# Board.net
KiCad netlist of a schematic drawn in EAGLE
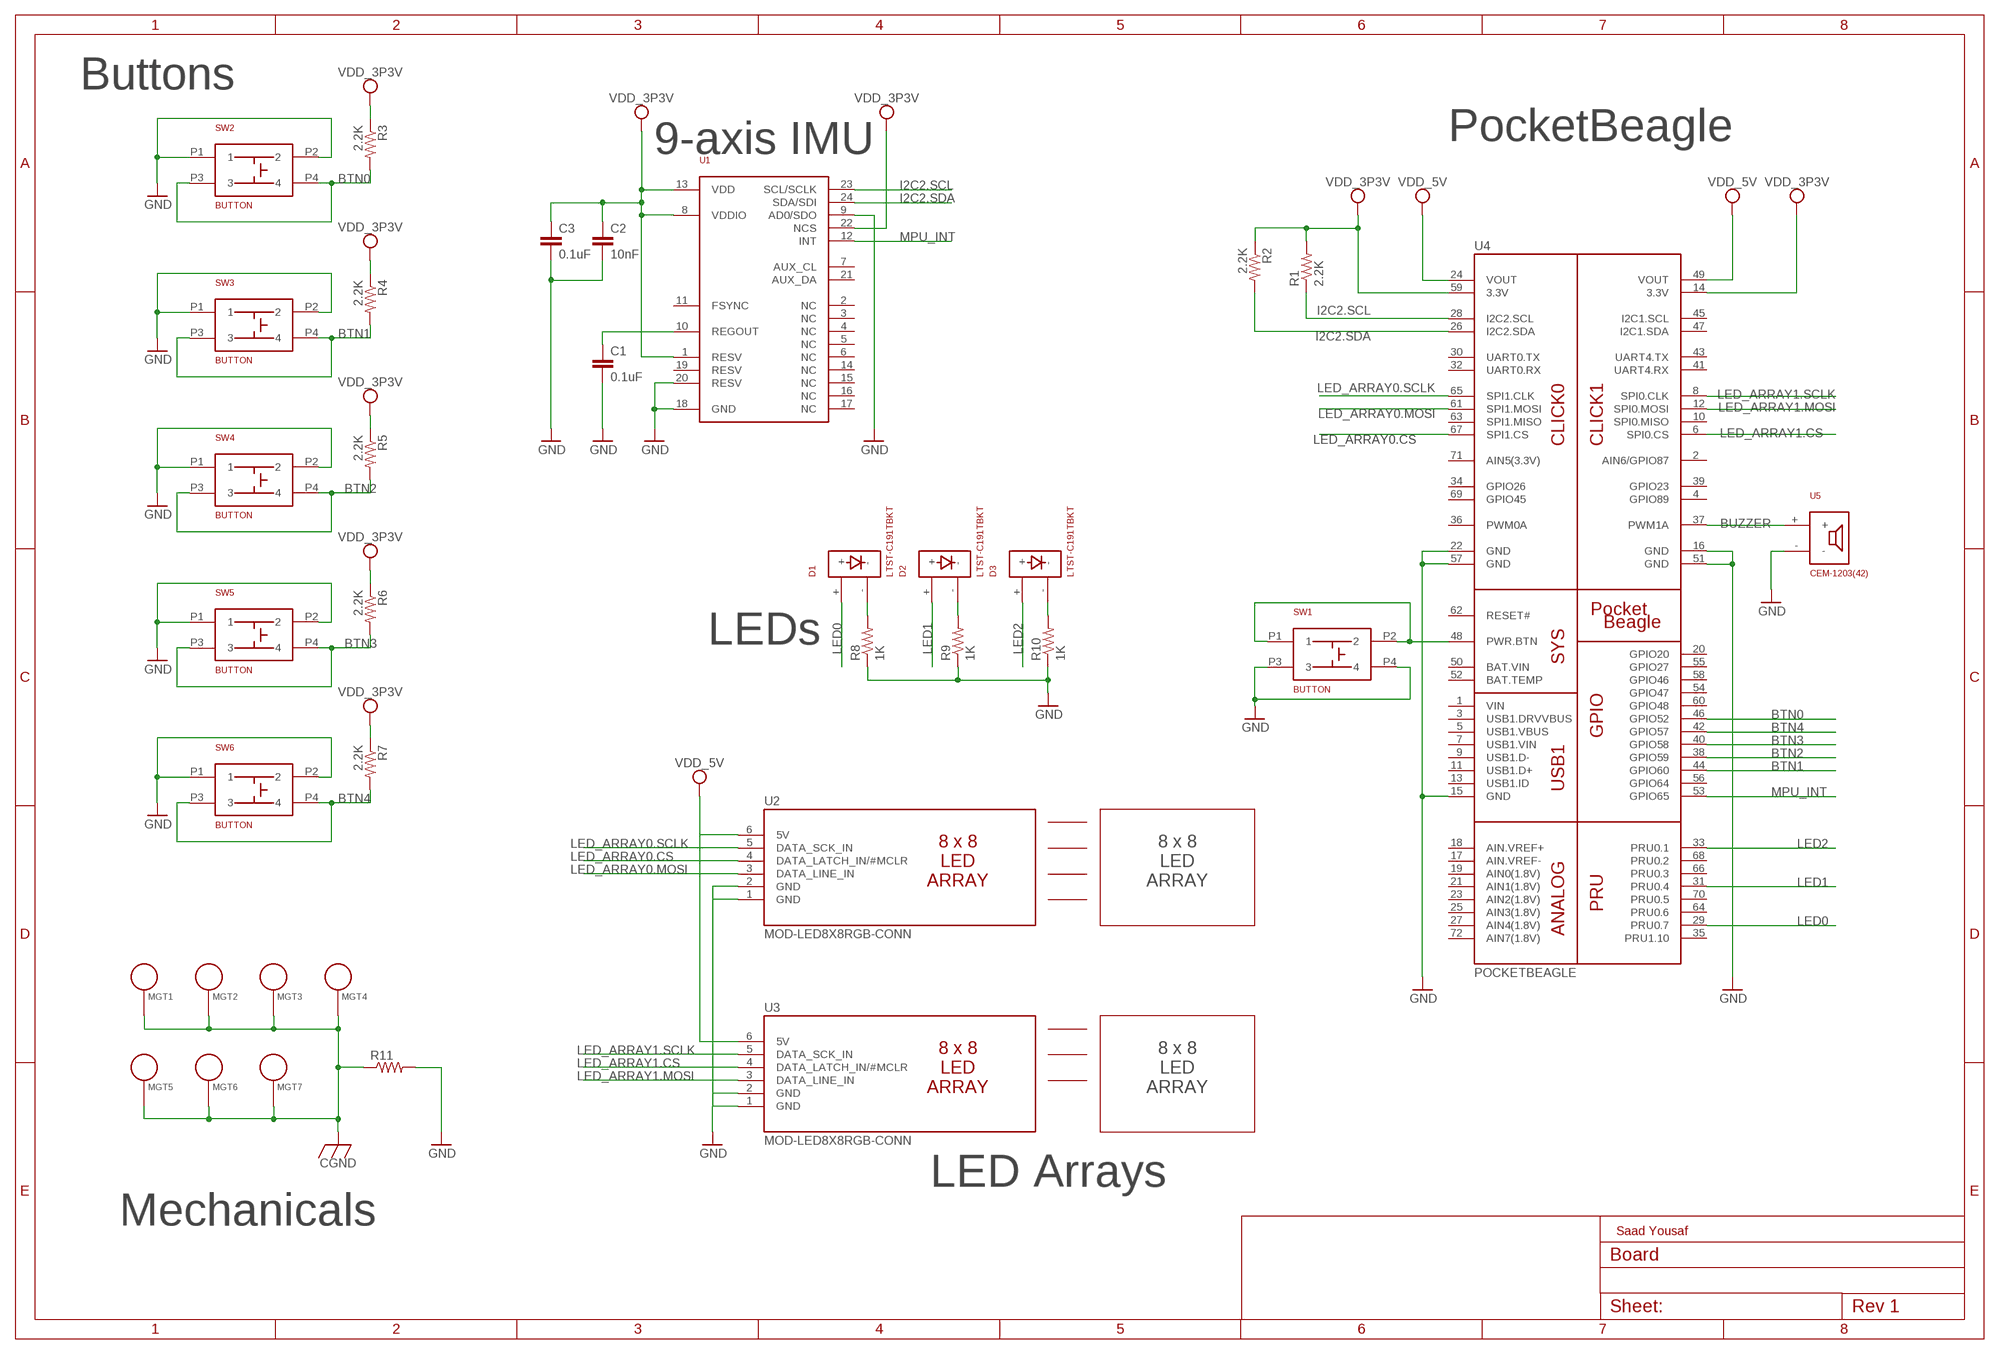
[diagram p0: schematic, sheet 1]

(export (version "E")
  (design (tool "Eeschema 10.0.6"))
  (components
    (comp (ref "C1")
      (value "0.1uF")
      (footprint "eagle-import:C0603")
      (libsource (lib "eagle-import") (part "C_C0603"))
    )
    (comp (ref "C2")
      (value "10nF")
      (footprint "eagle-import:C0603")
      (libsource (lib "eagle-import") (part "C_C0603"))
    )
    (comp (ref "C3")
      (value "0.1uF")
      (footprint "eagle-import:C0603")
      (libsource (lib "eagle-import") (part "C_C0603"))
    )
    (comp (ref "D1")
      (value "LTST-C191TBKT")
      (footprint "eagle-import:SMD-LED")
      (libsource (lib "eagle-import") (part "LTST-C191TBKT"))
    )
    (comp (ref "D2")
      (value "LTST-C191TBKT")
      (footprint "eagle-import:SMD-LED")
      (libsource (lib "eagle-import") (part "LTST-C191TBKT"))
    )
    (comp (ref "D3")
      (value "LTST-C191TBKT")
      (footprint "eagle-import:SMD-LED")
      (libsource (lib "eagle-import") (part "LTST-C191TBKT"))
    )
    (comp (ref "MGT1")
      (value "MOUNTING_HOLE")
      (footprint "eagle-import:MOUNTING_HOLE")
      (libsource (lib "eagle-import") (part "MOUNTING_HOLE"))
    )
    (comp (ref "MGT2")
      (value "MOUNTING_HOLE")
      (footprint "eagle-import:MOUNTING_HOLE")
      (libsource (lib "eagle-import") (part "MOUNTING_HOLE"))
    )
    (comp (ref "MGT3")
      (value "MOUNTING_HOLE")
      (footprint "eagle-import:MOUNTING_HOLE")
      (libsource (lib "eagle-import") (part "MOUNTING_HOLE"))
    )
    (comp (ref "MGT4")
      (value "MOUNTING_HOLE")
      (footprint "eagle-import:MOUNTING_HOLE")
      (libsource (lib "eagle-import") (part "MOUNTING_HOLE"))
    )
    (comp (ref "MGT5")
      (value "MOUNTING_HOLE")
      (footprint "eagle-import:MOUNTING_HOLE")
      (libsource (lib "eagle-import") (part "MOUNTING_HOLE"))
    )
    (comp (ref "MGT6")
      (value "MOUNTING_HOLE")
      (footprint "eagle-import:MOUNTING_HOLE")
      (libsource (lib "eagle-import") (part "MOUNTING_HOLE"))
    )
    (comp (ref "MGT7")
      (value "MOUNTING_HOLE")
      (footprint "eagle-import:MOUNTING_HOLE")
      (libsource (lib "eagle-import") (part "MOUNTING_HOLE"))
    )
    (comp (ref "R1")
      (value "2.2K")
      (footprint "eagle-import:R0603")
      (libsource (lib "eagle-import") (part "R_R0603"))
    )
    (comp (ref "R2")
      (value "2.2K")
      (footprint "eagle-import:R0603")
      (libsource (lib "eagle-import") (part "R_R0603"))
    )
    (comp (ref "R3")
      (value "2.2K")
      (footprint "eagle-import:R0603")
      (libsource (lib "eagle-import") (part "R_R0603"))
    )
    (comp (ref "R4")
      (value "2.2K")
      (footprint "eagle-import:R0603")
      (libsource (lib "eagle-import") (part "R_R0603"))
    )
    (comp (ref "R5")
      (value "2.2K")
      (footprint "eagle-import:R0603")
      (libsource (lib "eagle-import") (part "R_R0603"))
    )
    (comp (ref "R6")
      (value "2.2K")
      (footprint "eagle-import:R0603")
      (libsource (lib "eagle-import") (part "R_R0603"))
    )
    (comp (ref "R7")
      (value "2.2K")
      (footprint "eagle-import:R0603")
      (libsource (lib "eagle-import") (part "R_R0603"))
    )
    (comp (ref "R8")
      (value "1K")
      (footprint "eagle-import:R0603")
      (libsource (lib "eagle-import") (part "R_R0603"))
    )
    (comp (ref "R9")
      (value "1K")
      (footprint "eagle-import:R0603")
      (libsource (lib "eagle-import") (part "R_R0603"))
    )
    (comp (ref "R10")
      (value "1K")
      (footprint "eagle-import:R0603")
      (libsource (lib "eagle-import") (part "R_R0603"))
    )
    (comp (ref "R11")
      (value "R_R0603")
      (footprint "eagle-import:R0603")
      (libsource (lib "eagle-import") (part "R_R0603"))
    )
    (comp (ref "SW1")
      (value "BUTTON")
      (footprint "eagle-import:BTN")
      (libsource (lib "eagle-import") (part "BUTTON"))
    )
    (comp (ref "SW2")
      (value "BUTTON")
      (footprint "eagle-import:BTN")
      (libsource (lib "eagle-import") (part "BUTTON"))
    )
    (comp (ref "SW3")
      (value "BUTTON")
      (footprint "eagle-import:BTN")
      (libsource (lib "eagle-import") (part "BUTTON"))
    )
    (comp (ref "SW4")
      (value "BUTTON")
      (footprint "eagle-import:BTN")
      (libsource (lib "eagle-import") (part "BUTTON"))
    )
    (comp (ref "SW5")
      (value "BUTTON")
      (footprint "eagle-import:BTN")
      (libsource (lib "eagle-import") (part "BUTTON"))
    )
    (comp (ref "SW6")
      (value "BUTTON")
      (footprint "eagle-import:BTN")
      (libsource (lib "eagle-import") (part "BUTTON"))
    )
    (comp (ref "U1")
      (value "MPU-9250")
      (footprint "eagle-import:QFN-3MMX3MM")
      (libsource (lib "eagle-import") (part "MPU-9250"))
    )
    (comp (ref "U2")
      (value "MOD-LED8X8RGB-CONN")
      (footprint "eagle-import:FE06W")
      (libsource (lib "eagle-import") (part "MOD-LED8X8RGB-CONN"))
    )
    (comp (ref "U3")
      (value "MOD-LED8X8RGB-CONN")
      (footprint "eagle-import:FE06W")
      (libsource (lib "eagle-import") (part "MOD-LED8X8RGB-CONN"))
    )
    (comp (ref "U4")
      (value "POCKETBEAGLE")
      (footprint "eagle-import:POCKETBEAGLE")
      (libsource (lib "eagle-import") (part "POCKETBEAGLE"))
    )
    (comp (ref "U5")
      (value "CEM-1203(42)")
      (footprint "eagle-import:CEM-1203(42)")
      (libsource (lib "eagle-import") (part "CEM-1203(42)"))
    )
  )
  (nets
    (net (code "1") (name "/BTN0") (class "Default")
      (node (ref "R3") (pin "2") (pinfunction "2_2") (pintype "passive"))
      (node (ref "SW2") (pin "P3") (pinfunction "3_P3") (pintype "bidirectional"))
      (node (ref "SW2") (pin "P4") (pinfunction "4_P4") (pintype "bidirectional"))
      (node (ref "U4") (pin "46") (pinfunction "GPIO52_46") (pintype "bidirectional"))
    )
    (net (code "2") (name "/BTN1") (class "Default")
      (node (ref "R4") (pin "2") (pinfunction "2_2") (pintype "passive"))
      (node (ref "SW3") (pin "P3") (pinfunction "3_P3") (pintype "bidirectional"))
      (node (ref "SW3") (pin "P4") (pinfunction "4_P4") (pintype "bidirectional"))
      (node (ref "U4") (pin "44") (pinfunction "GPIO60_44") (pintype "bidirectional"))
    )
    (net (code "3") (name "/BTN2") (class "Default")
      (node (ref "R5") (pin "2") (pinfunction "2_2") (pintype "passive"))
      (node (ref "SW4") (pin "P3") (pinfunction "3_P3") (pintype "bidirectional"))
      (node (ref "SW4") (pin "P4") (pinfunction "4_P4") (pintype "bidirectional"))
      (node (ref "U4") (pin "38") (pinfunction "GPIO59_38") (pintype "bidirectional"))
    )
    (net (code "4") (name "/BTN3") (class "Default")
      (node (ref "R6") (pin "2") (pinfunction "2_2") (pintype "passive"))
      (node (ref "SW5") (pin "P3") (pinfunction "3_P3") (pintype "bidirectional"))
      (node (ref "SW5") (pin "P4") (pinfunction "4_P4") (pintype "bidirectional"))
      (node (ref "U4") (pin "40") (pinfunction "GPIO58_40") (pintype "bidirectional"))
    )
    (net (code "5") (name "/BTN4") (class "Default")
      (node (ref "R7") (pin "2") (pinfunction "2_2") (pintype "passive"))
      (node (ref "SW6") (pin "P3") (pinfunction "3_P3") (pintype "bidirectional"))
      (node (ref "SW6") (pin "P4") (pinfunction "4_P4") (pintype "bidirectional"))
      (node (ref "U4") (pin "42") (pinfunction "GPIO57_42") (pintype "bidirectional"))
    )
    (net (code "6") (name "/BUZZER") (class "Default")
      (node (ref "U4") (pin "37") (pinfunction "PWM1A_37") (pintype "bidirectional"))
      (node (ref "U5") (pin "+") (pinfunction "+_+") (pintype "bidirectional"))
    )
    (net (code "7") (name "/I2C2.SCL") (class "Default")
      (node (ref "R1") (pin "1") (pinfunction "1_1") (pintype "passive"))
      (node (ref "U1") (pin "23") (pinfunction "SCL/SCLK_23") (pintype "bidirectional"))
      (node (ref "U4") (pin "28") (pinfunction "I2C2.SCL_28") (pintype "bidirectional"))
    )
    (net (code "8") (name "/I2C2.SDA") (class "Default")
      (node (ref "R2") (pin "2") (pinfunction "2_2") (pintype "passive"))
      (node (ref "U1") (pin "24") (pinfunction "SDA/SDI_24") (pintype "bidirectional"))
      (node (ref "U4") (pin "26") (pinfunction "I2C2.SDA_26") (pintype "bidirectional"))
    )
    (net (code "9") (name "/LED0") (class "Default")
      (node (ref "D1") (pin "+") (pinfunction "+_+") (pintype "bidirectional"))
      (node (ref "U4") (pin "29") (pinfunction "PRU0.7_29") (pintype "bidirectional"))
    )
    (net (code "10") (name "/LED1") (class "Default")
      (node (ref "D2") (pin "+") (pinfunction "+_+") (pintype "bidirectional"))
      (node (ref "U4") (pin "31") (pinfunction "PRU0.4_31") (pintype "bidirectional"))
    )
    (net (code "11") (name "/LED2") (class "Default")
      (node (ref "D3") (pin "+") (pinfunction "+_+") (pintype "bidirectional"))
      (node (ref "U4") (pin "33") (pinfunction "PRU0.1_33") (pintype "bidirectional"))
    )
    (net (code "12") (name "/LED_ARRAY0.CS") (class "Default")
      (node (ref "U2") (pin "4") (pinfunction "DATA_LATCH_IN/#MCLR_4") (pintype "bidirectional"))
      (node (ref "U4") (pin "67") (pinfunction "SPI1.CS_67") (pintype "bidirectional"))
    )
    (net (code "13") (name "/LED_ARRAY0.MOSI") (class "Default")
      (node (ref "U2") (pin "3") (pinfunction "DATA_LINE_IN_3") (pintype "bidirectional"))
      (node (ref "U4") (pin "61") (pinfunction "SPI1.MOSI_61") (pintype "bidirectional"))
    )
    (net (code "14") (name "/LED_ARRAY0.SCLK") (class "Default")
      (node (ref "U2") (pin "5") (pinfunction "DATA_SCK_IN_5") (pintype "bidirectional"))
      (node (ref "U4") (pin "65") (pinfunction "SPI1.CLK_65") (pintype "bidirectional"))
    )
    (net (code "15") (name "/LED_ARRAY1.CS") (class "Default")
      (node (ref "U3") (pin "4") (pinfunction "DATA_LATCH_IN/#MCLR_4") (pintype "bidirectional"))
      (node (ref "U4") (pin "6") (pinfunction "SPI0.CS_6") (pintype "bidirectional"))
    )
    (net (code "16") (name "/LED_ARRAY1.MOSI") (class "Default")
      (node (ref "U3") (pin "3") (pinfunction "DATA_LINE_IN_3") (pintype "bidirectional"))
      (node (ref "U4") (pin "12") (pinfunction "SPI0.MOSI_12") (pintype "bidirectional"))
    )
    (net (code "17") (name "/LED_ARRAY1.SCLK") (class "Default")
      (node (ref "U3") (pin "5") (pinfunction "DATA_SCK_IN_5") (pintype "bidirectional"))
      (node (ref "U4") (pin "8") (pinfunction "SPI0.CLK_8") (pintype "bidirectional"))
    )
    (net (code "18") (name "/MPU_INT") (class "Default")
      (node (ref "U1") (pin "12") (pinfunction "INT_12") (pintype "bidirectional"))
      (node (ref "U4") (pin "53") (pinfunction "GPIO65_53") (pintype "bidirectional"))
    )
    (net (code "19") (name "CGND") (class "Default")
      (node (ref "MGT1") (pin "P$1") (pinfunction "P$1_P$1") (pintype "bidirectional"))
      (node (ref "MGT2") (pin "P$1") (pinfunction "P$1_P$1") (pintype "bidirectional"))
      (node (ref "MGT3") (pin "P$1") (pinfunction "P$1_P$1") (pintype "bidirectional"))
      (node (ref "MGT4") (pin "P$1") (pinfunction "P$1_P$1") (pintype "bidirectional"))
      (node (ref "MGT5") (pin "P$1") (pinfunction "P$1_P$1") (pintype "bidirectional"))
      (node (ref "MGT6") (pin "P$1") (pinfunction "P$1_P$1") (pintype "bidirectional"))
      (node (ref "MGT7") (pin "P$1") (pinfunction "P$1_P$1") (pintype "bidirectional"))
      (node (ref "R11") (pin "1") (pinfunction "1_1") (pintype "passive"))
    )
    (net (code "20") (name "GND") (class "Default")
      (node (ref "C1") (pin "2") (pinfunction "2_2") (pintype "passive"))
      (node (ref "C2") (pin "2") (pinfunction "2_2") (pintype "passive"))
      (node (ref "C3") (pin "2") (pinfunction "2_2") (pintype "passive"))
      (node (ref "R10") (pin "1") (pinfunction "1_1") (pintype "passive"))
      (node (ref "R11") (pin "2") (pinfunction "2_2") (pintype "passive"))
      (node (ref "R8") (pin "1") (pinfunction "1_1") (pintype "passive"))
      (node (ref "R9") (pin "1") (pinfunction "1_1") (pintype "passive"))
      (node (ref "SW1") (pin "P3") (pinfunction "3_P3") (pintype "bidirectional"))
      (node (ref "SW1") (pin "P4") (pinfunction "4_P4") (pintype "bidirectional"))
      (node (ref "SW2") (pin "P1") (pinfunction "1_P1") (pintype "bidirectional"))
      (node (ref "SW2") (pin "P2") (pinfunction "2_P2") (pintype "bidirectional"))
      (node (ref "SW3") (pin "P1") (pinfunction "1_P1") (pintype "bidirectional"))
      (node (ref "SW3") (pin "P2") (pinfunction "2_P2") (pintype "bidirectional"))
      (node (ref "SW4") (pin "P1") (pinfunction "1_P1") (pintype "bidirectional"))
      (node (ref "SW4") (pin "P2") (pinfunction "2_P2") (pintype "bidirectional"))
      (node (ref "SW5") (pin "P1") (pinfunction "1_P1") (pintype "bidirectional"))
      (node (ref "SW5") (pin "P2") (pinfunction "2_P2") (pintype "bidirectional"))
      (node (ref "SW6") (pin "P1") (pinfunction "1_P1") (pintype "bidirectional"))
      (node (ref "SW6") (pin "P2") (pinfunction "2_P2") (pintype "bidirectional"))
      (node (ref "U1") (pin "18") (pinfunction "GND_18") (pintype "bidirectional"))
      (node (ref "U1") (pin "20") (pinfunction "RESV_20") (pintype "bidirectional"))
      (node (ref "U1") (pin "9") (pinfunction "AD0/SDO_9") (pintype "bidirectional"))
      (node (ref "U2") (pin "1") (pinfunction "GND_1") (pintype "bidirectional"))
      (node (ref "U2") (pin "2") (pinfunction "GND_2") (pintype "bidirectional"))
      (node (ref "U3") (pin "1") (pinfunction "GND_1") (pintype "bidirectional"))
      (node (ref "U3") (pin "2") (pinfunction "GND_2") (pintype "bidirectional"))
      (node (ref "U4") (pin "15") (pinfunction "GND_15") (pintype "bidirectional"))
      (node (ref "U4") (pin "16") (pinfunction "GND_16") (pintype "bidirectional"))
      (node (ref "U4") (pin "22") (pinfunction "GND_22") (pintype "bidirectional"))
      (node (ref "U4") (pin "51") (pinfunction "GND_51") (pintype "bidirectional"))
      (node (ref "U4") (pin "57") (pinfunction "GND_57") (pintype "bidirectional"))
      (node (ref "U5") (pin "-") (pinfunction "-_-") (pintype "bidirectional"))
    )
    (net (code "21") (name "Net-(D1-Pad-)") (class "Default")
      (node (ref "D1") (pin "-") (pinfunction "-_-") (pintype "bidirectional"))
      (node (ref "R8") (pin "2") (pinfunction "2_2") (pintype "passive"))
    )
    (net (code "22") (name "Net-(D2-Pad-)") (class "Default")
      (node (ref "D2") (pin "-") (pinfunction "-_-") (pintype "bidirectional"))
      (node (ref "R9") (pin "2") (pinfunction "2_2") (pintype "passive"))
    )
    (net (code "23") (name "Net-(D3-Pad-)") (class "Default")
      (node (ref "D3") (pin "-") (pinfunction "-_-") (pintype "bidirectional"))
      (node (ref "R10") (pin "2") (pinfunction "2_2") (pintype "passive"))
    )
    (net (code "24") (name "Net-(SW1-1)") (class "Default")
      (node (ref "SW1") (pin "P1") (pinfunction "1_P1") (pintype "bidirectional"))
      (node (ref "SW1") (pin "P2") (pinfunction "2_P2") (pintype "bidirectional"))
      (node (ref "U4") (pin "48") (pinfunction "PWR.BTN_48") (pintype "bidirectional"))
    )
    (net (code "25") (name "Net-(U1-REGOUT)") (class "Default")
      (node (ref "C1") (pin "1") (pinfunction "1_1") (pintype "passive"))
      (node (ref "U1") (pin "10") (pinfunction "REGOUT_10") (pintype "bidirectional"))
    )
    (net (code "26") (name "VDD_3P3V") (class "Default")
      (node (ref "C2") (pin "1") (pinfunction "1_1") (pintype "passive"))
      (node (ref "C3") (pin "1") (pinfunction "1_1") (pintype "passive"))
      (node (ref "R1") (pin "2") (pinfunction "2_2") (pintype "passive"))
      (node (ref "R2") (pin "1") (pinfunction "1_1") (pintype "passive"))
      (node (ref "R3") (pin "1") (pinfunction "1_1") (pintype "passive"))
      (node (ref "R4") (pin "1") (pinfunction "1_1") (pintype "passive"))
      (node (ref "R5") (pin "1") (pinfunction "1_1") (pintype "passive"))
      (node (ref "R6") (pin "1") (pinfunction "1_1") (pintype "passive"))
      (node (ref "R7") (pin "1") (pinfunction "1_1") (pintype "passive"))
      (node (ref "U1") (pin "1") (pinfunction "RESV_1") (pintype "bidirectional"))
      (node (ref "U1") (pin "13") (pinfunction "VDD_13") (pintype "bidirectional"))
      (node (ref "U1") (pin "22") (pinfunction "NCS_22") (pintype "bidirectional"))
      (node (ref "U1") (pin "8") (pinfunction "VDDIO_8") (pintype "bidirectional"))
      (node (ref "U2") (pin "6") (pinfunction "5V_6") (pintype "bidirectional"))
      (node (ref "U3") (pin "6") (pinfunction "5V_6") (pintype "bidirectional"))
      (node (ref "U4") (pin "14") (pinfunction "3.3V_14") (pintype "bidirectional"))
      (node (ref "U4") (pin "24") (pinfunction "VOUT_24") (pintype "bidirectional"))
      (node (ref "U4") (pin "49") (pinfunction "VOUT_49") (pintype "bidirectional"))
      (node (ref "U4") (pin "59") (pinfunction "3.3V_59") (pintype "bidirectional"))
    )
    (net (code "27") (name "unconnected-(U1-AUX_CL-Pad7)") (class "Default")
      (node (ref "U1") (pin "7") (pinfunction "AUX_CL_7") (pintype "bidirectional"))
    )
    (net (code "28") (name "unconnected-(U1-AUX_DA-Pad21)") (class "Default")
      (node (ref "U1") (pin "21") (pinfunction "AUX_DA_21") (pintype "bidirectional"))
    )
    (net (code "29") (name "unconnected-(U1-FSYNC-Pad11)") (class "Default")
      (node (ref "U1") (pin "11") (pinfunction "FSYNC_11") (pintype "bidirectional"))
    )
    (net (code "30") (name "unconnected-(U1-NC-Pad2)") (class "Default")
      (node (ref "U1") (pin "2") (pinfunction "NC_2") (pintype "bidirectional"))
    )
    (net (code "31") (name "unconnected-(U1-NC-Pad3)") (class "Default")
      (node (ref "U1") (pin "3") (pinfunction "NC_3") (pintype "bidirectional"))
    )
    (net (code "32") (name "unconnected-(U1-NC-Pad4)") (class "Default")
      (node (ref "U1") (pin "4") (pinfunction "NC_4") (pintype "bidirectional"))
    )
    (net (code "33") (name "unconnected-(U1-NC-Pad5)") (class "Default")
      (node (ref "U1") (pin "5") (pinfunction "NC_5") (pintype "bidirectional"))
    )
    (net (code "34") (name "unconnected-(U1-NC-Pad6)") (class "Default")
      (node (ref "U1") (pin "6") (pinfunction "NC_6") (pintype "bidirectional"))
    )
    (net (code "35") (name "unconnected-(U1-NC-Pad14)") (class "Default")
      (node (ref "U1") (pin "14") (pinfunction "NC_14") (pintype "bidirectional"))
    )
    (net (code "36") (name "unconnected-(U1-NC-Pad15)") (class "Default")
      (node (ref "U1") (pin "15") (pinfunction "NC_15") (pintype "bidirectional"))
    )
    (net (code "37") (name "unconnected-(U1-NC-Pad16)") (class "Default")
      (node (ref "U1") (pin "16") (pinfunction "NC_16") (pintype "bidirectional"))
    )
    (net (code "38") (name "unconnected-(U1-NC-Pad17)") (class "Default")
      (node (ref "U1") (pin "17") (pinfunction "NC_17") (pintype "bidirectional"))
    )
    (net (code "39") (name "unconnected-(U1-RESV-Pad19)") (class "Default")
      (node (ref "U1") (pin "19") (pinfunction "RESV_19") (pintype "bidirectional"))
    )
    (net (code "40") (name "unconnected-(U4-AIN.VREF+-Pad18)") (class "Default")
      (node (ref "U4") (pin "18") (pinfunction "AIN.VREF+_18") (pintype "bidirectional"))
    )
    (net (code "41") (name "unconnected-(U4-AIN.VREF--Pad17)") (class "Default")
      (node (ref "U4") (pin "17") (pinfunction "AIN.VREF-_17") (pintype "bidirectional"))
    )
    (net (code "42") (name "unconnected-(U4-AIN0(1.8V)-Pad19)") (class "Default")
      (node (ref "U4") (pin "19") (pinfunction "AIN0(1.8V)_19") (pintype "bidirectional"))
    )
    (net (code "43") (name "unconnected-(U4-AIN1(1.8V)-Pad21)") (class "Default")
      (node (ref "U4") (pin "21") (pinfunction "AIN1(1.8V)_21") (pintype "bidirectional"))
    )
    (net (code "44") (name "unconnected-(U4-AIN2(1.8V)-Pad23)") (class "Default")
      (node (ref "U4") (pin "23") (pinfunction "AIN2(1.8V)_23") (pintype "bidirectional"))
    )
    (net (code "45") (name "unconnected-(U4-AIN3(1.8V)-Pad25)") (class "Default")
      (node (ref "U4") (pin "25") (pinfunction "AIN3(1.8V)_25") (pintype "bidirectional"))
    )
    (net (code "46") (name "unconnected-(U4-AIN4(1.8V)-Pad27)") (class "Default")
      (node (ref "U4") (pin "27") (pinfunction "AIN4(1.8V)_27") (pintype "bidirectional"))
    )
    (net (code "47") (name "unconnected-(U4-AIN5(3.3V)-Pad71)") (class "Default")
      (node (ref "U4") (pin "71") (pinfunction "AIN5(3.3V)_71") (pintype "bidirectional"))
    )
    (net (code "48") (name "unconnected-(U4-AIN6{slash}GPIO87-Pad2)") (class "Default")
      (node (ref "U4") (pin "2") (pinfunction "AIN6/GPIO87_2") (pintype "bidirectional"))
    )
    (net (code "49") (name "unconnected-(U4-AIN7(1.8V)-Pad72)") (class "Default")
      (node (ref "U4") (pin "72") (pinfunction "AIN7(1.8V)_72") (pintype "bidirectional"))
    )
    (net (code "50") (name "unconnected-(U4-BAT.TEMP-Pad52)") (class "Default")
      (node (ref "U4") (pin "52") (pinfunction "BAT.TEMP_52") (pintype "bidirectional"))
    )
    (net (code "51") (name "unconnected-(U4-BAT.VIN-Pad50)") (class "Default")
      (node (ref "U4") (pin "50") (pinfunction "BAT.VIN_50") (pintype "bidirectional"))
    )
    (net (code "52") (name "unconnected-(U4-GPIO20-Pad20)") (class "Default")
      (node (ref "U4") (pin "20") (pinfunction "GPIO20_20") (pintype "bidirectional"))
    )
    (net (code "53") (name "unconnected-(U4-GPIO23-Pad39)") (class "Default")
      (node (ref "U4") (pin "39") (pinfunction "GPIO23_39") (pintype "bidirectional"))
    )
    (net (code "54") (name "unconnected-(U4-GPIO26-Pad34)") (class "Default")
      (node (ref "U4") (pin "34") (pinfunction "GPIO26_34") (pintype "bidirectional"))
    )
    (net (code "55") (name "unconnected-(U4-GPIO27-Pad55)") (class "Default")
      (node (ref "U4") (pin "55") (pinfunction "GPIO27_55") (pintype "bidirectional"))
    )
    (net (code "56") (name "unconnected-(U4-GPIO45-Pad69)") (class "Default")
      (node (ref "U4") (pin "69") (pinfunction "GPIO45_69") (pintype "bidirectional"))
    )
    (net (code "57") (name "unconnected-(U4-GPIO46-Pad58)") (class "Default")
      (node (ref "U4") (pin "58") (pinfunction "GPIO46_58") (pintype "bidirectional"))
    )
    (net (code "58") (name "unconnected-(U4-GPIO47-Pad54)") (class "Default")
      (node (ref "U4") (pin "54") (pinfunction "GPIO47_54") (pintype "bidirectional"))
    )
    (net (code "59") (name "unconnected-(U4-GPIO48-Pad60)") (class "Default")
      (node (ref "U4") (pin "60") (pinfunction "GPIO48_60") (pintype "bidirectional"))
    )
    (net (code "60") (name "unconnected-(U4-GPIO64-Pad56)") (class "Default")
      (node (ref "U4") (pin "56") (pinfunction "GPIO64_56") (pintype "bidirectional"))
    )
    (net (code "61") (name "unconnected-(U4-GPIO89-Pad4)") (class "Default")
      (node (ref "U4") (pin "4") (pinfunction "GPIO89_4") (pintype "bidirectional"))
    )
    (net (code "62") (name "unconnected-(U4-I2C1.SCL-Pad45)") (class "Default")
      (node (ref "U4") (pin "45") (pinfunction "I2C1.SCL_45") (pintype "bidirectional"))
    )
    (net (code "63") (name "unconnected-(U4-I2C1.SDA-Pad47)") (class "Default")
      (node (ref "U4") (pin "47") (pinfunction "I2C1.SDA_47") (pintype "bidirectional"))
    )
    (net (code "64") (name "unconnected-(U4-PRU0.2-Pad68)") (class "Default")
      (node (ref "U4") (pin "68") (pinfunction "PRU0.2_68") (pintype "bidirectional"))
    )
    (net (code "65") (name "unconnected-(U4-PRU0.3-Pad66)") (class "Default")
      (node (ref "U4") (pin "66") (pinfunction "PRU0.3_66") (pintype "bidirectional"))
    )
    (net (code "66") (name "unconnected-(U4-PRU0.5-Pad70)") (class "Default")
      (node (ref "U4") (pin "70") (pinfunction "PRU0.5_70") (pintype "bidirectional"))
    )
    (net (code "67") (name "unconnected-(U4-PRU0.6-Pad64)") (class "Default")
      (node (ref "U4") (pin "64") (pinfunction "PRU0.6_64") (pintype "bidirectional"))
    )
    (net (code "68") (name "unconnected-(U4-PRU1.10-Pad35)") (class "Default")
      (node (ref "U4") (pin "35") (pinfunction "PRU1.10_35") (pintype "bidirectional"))
    )
    (net (code "69") (name "unconnected-(U4-PWM0A-Pad36)") (class "Default")
      (node (ref "U4") (pin "36") (pinfunction "PWM0A_36") (pintype "bidirectional"))
    )
    (net (code "70") (name "unconnected-(U4-RESET#-Pad62)") (class "Default")
      (node (ref "U4") (pin "62") (pinfunction "RESET#_62") (pintype "bidirectional"))
    )
    (net (code "71") (name "unconnected-(U4-SPI0.MISO-Pad10)") (class "Default")
      (node (ref "U4") (pin "10") (pinfunction "SPI0.MISO_10") (pintype "bidirectional"))
    )
    (net (code "72") (name "unconnected-(U4-SPI1.MISO-Pad63)") (class "Default")
      (node (ref "U4") (pin "63") (pinfunction "SPI1.MISO_63") (pintype "bidirectional"))
    )
    (net (code "73") (name "unconnected-(U4-UART0.RX-Pad32)") (class "Default")
      (node (ref "U4") (pin "32") (pinfunction "UART0.RX_32") (pintype "bidirectional"))
    )
    (net (code "74") (name "unconnected-(U4-UART0.TX-Pad30)") (class "Default")
      (node (ref "U4") (pin "30") (pinfunction "UART0.TX_30") (pintype "bidirectional"))
    )
    (net (code "75") (name "unconnected-(U4-UART4.RX-Pad41)") (class "Default")
      (node (ref "U4") (pin "41") (pinfunction "UART4.RX_41") (pintype "bidirectional"))
    )
    (net (code "76") (name "unconnected-(U4-UART4.TX-Pad43)") (class "Default")
      (node (ref "U4") (pin "43") (pinfunction "UART4.TX_43") (pintype "bidirectional"))
    )
    (net (code "77") (name "unconnected-(U4-USB1.D+-Pad11)") (class "Default")
      (node (ref "U4") (pin "11") (pinfunction "USB1.D+_11") (pintype "bidirectional"))
    )
    (net (code "78") (name "unconnected-(U4-USB1.D--Pad9)") (class "Default")
      (node (ref "U4") (pin "9") (pinfunction "USB1.D-_9") (pintype "bidirectional"))
    )
    (net (code "79") (name "unconnected-(U4-USB1.DRVVBUS-Pad3)") (class "Default")
      (node (ref "U4") (pin "3") (pinfunction "USB1.DRVVBUS_3") (pintype "bidirectional"))
    )
    (net (code "80") (name "unconnected-(U4-USB1.ID-Pad13)") (class "Default")
      (node (ref "U4") (pin "13") (pinfunction "USB1.ID_13") (pintype "bidirectional"))
    )
    (net (code "81") (name "unconnected-(U4-USB1.VBUS-Pad5)") (class "Default")
      (node (ref "U4") (pin "5") (pinfunction "USB1.VBUS_5") (pintype "bidirectional"))
    )
    (net (code "82") (name "unconnected-(U4-USB1.VIN-Pad7)") (class "Default")
      (node (ref "U4") (pin "7") (pinfunction "USB1.VIN_7") (pintype "bidirectional"))
    )
    (net (code "83") (name "unconnected-(U4-VIN-Pad1)") (class "Default")
      (node (ref "U4") (pin "1") (pinfunction "VIN_1") (pintype "bidirectional"))
    )
  )
)
